# saha-cpu.net
KiCad netlist of a schematic drawn in EAGLE
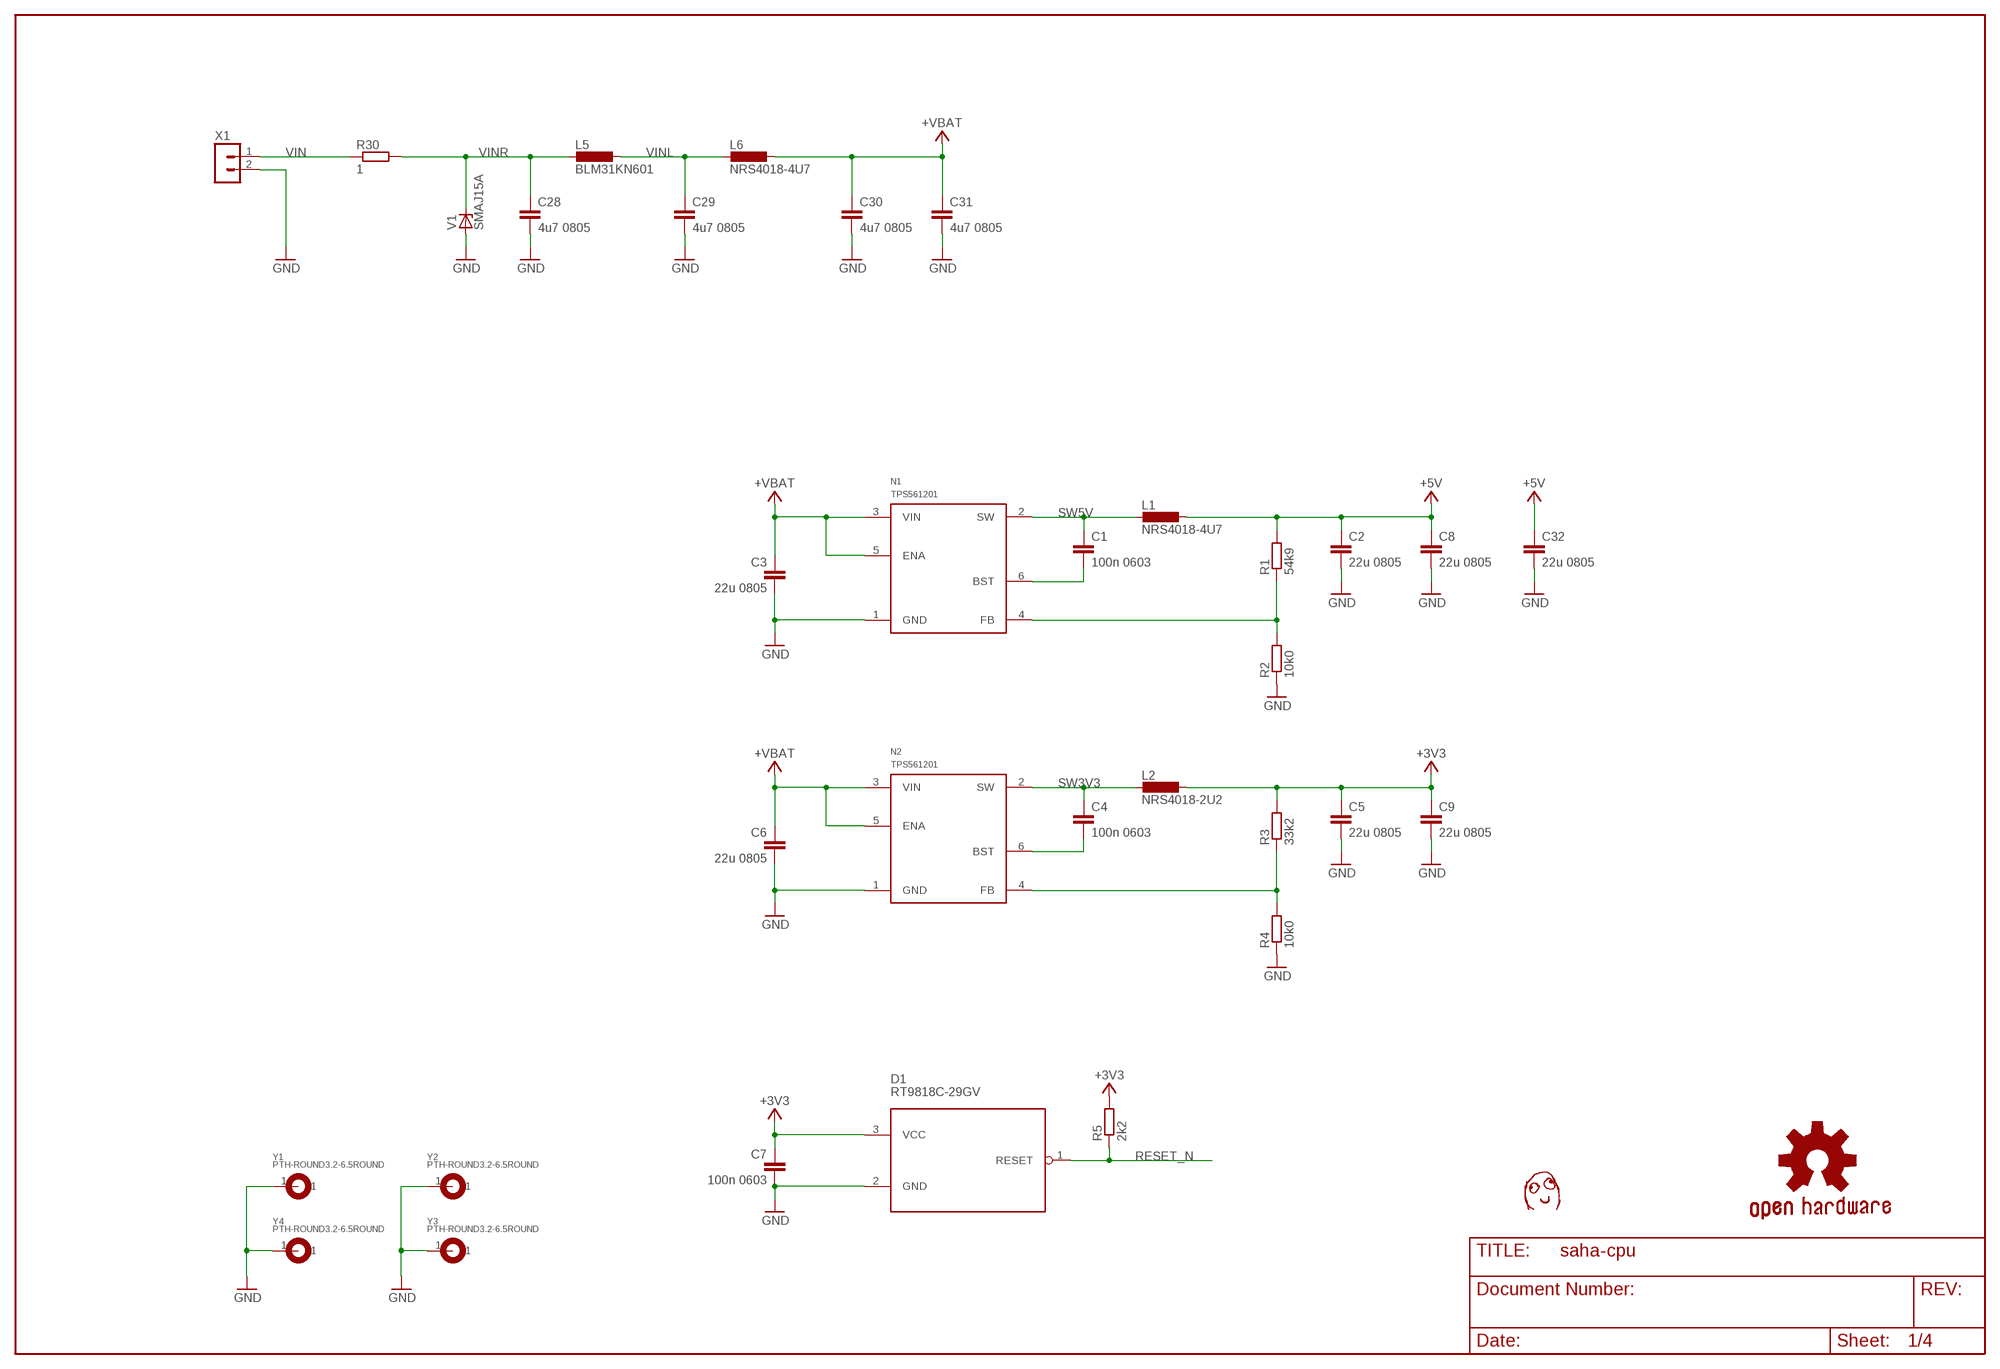
[diagram p0: schematic, sheet 1]
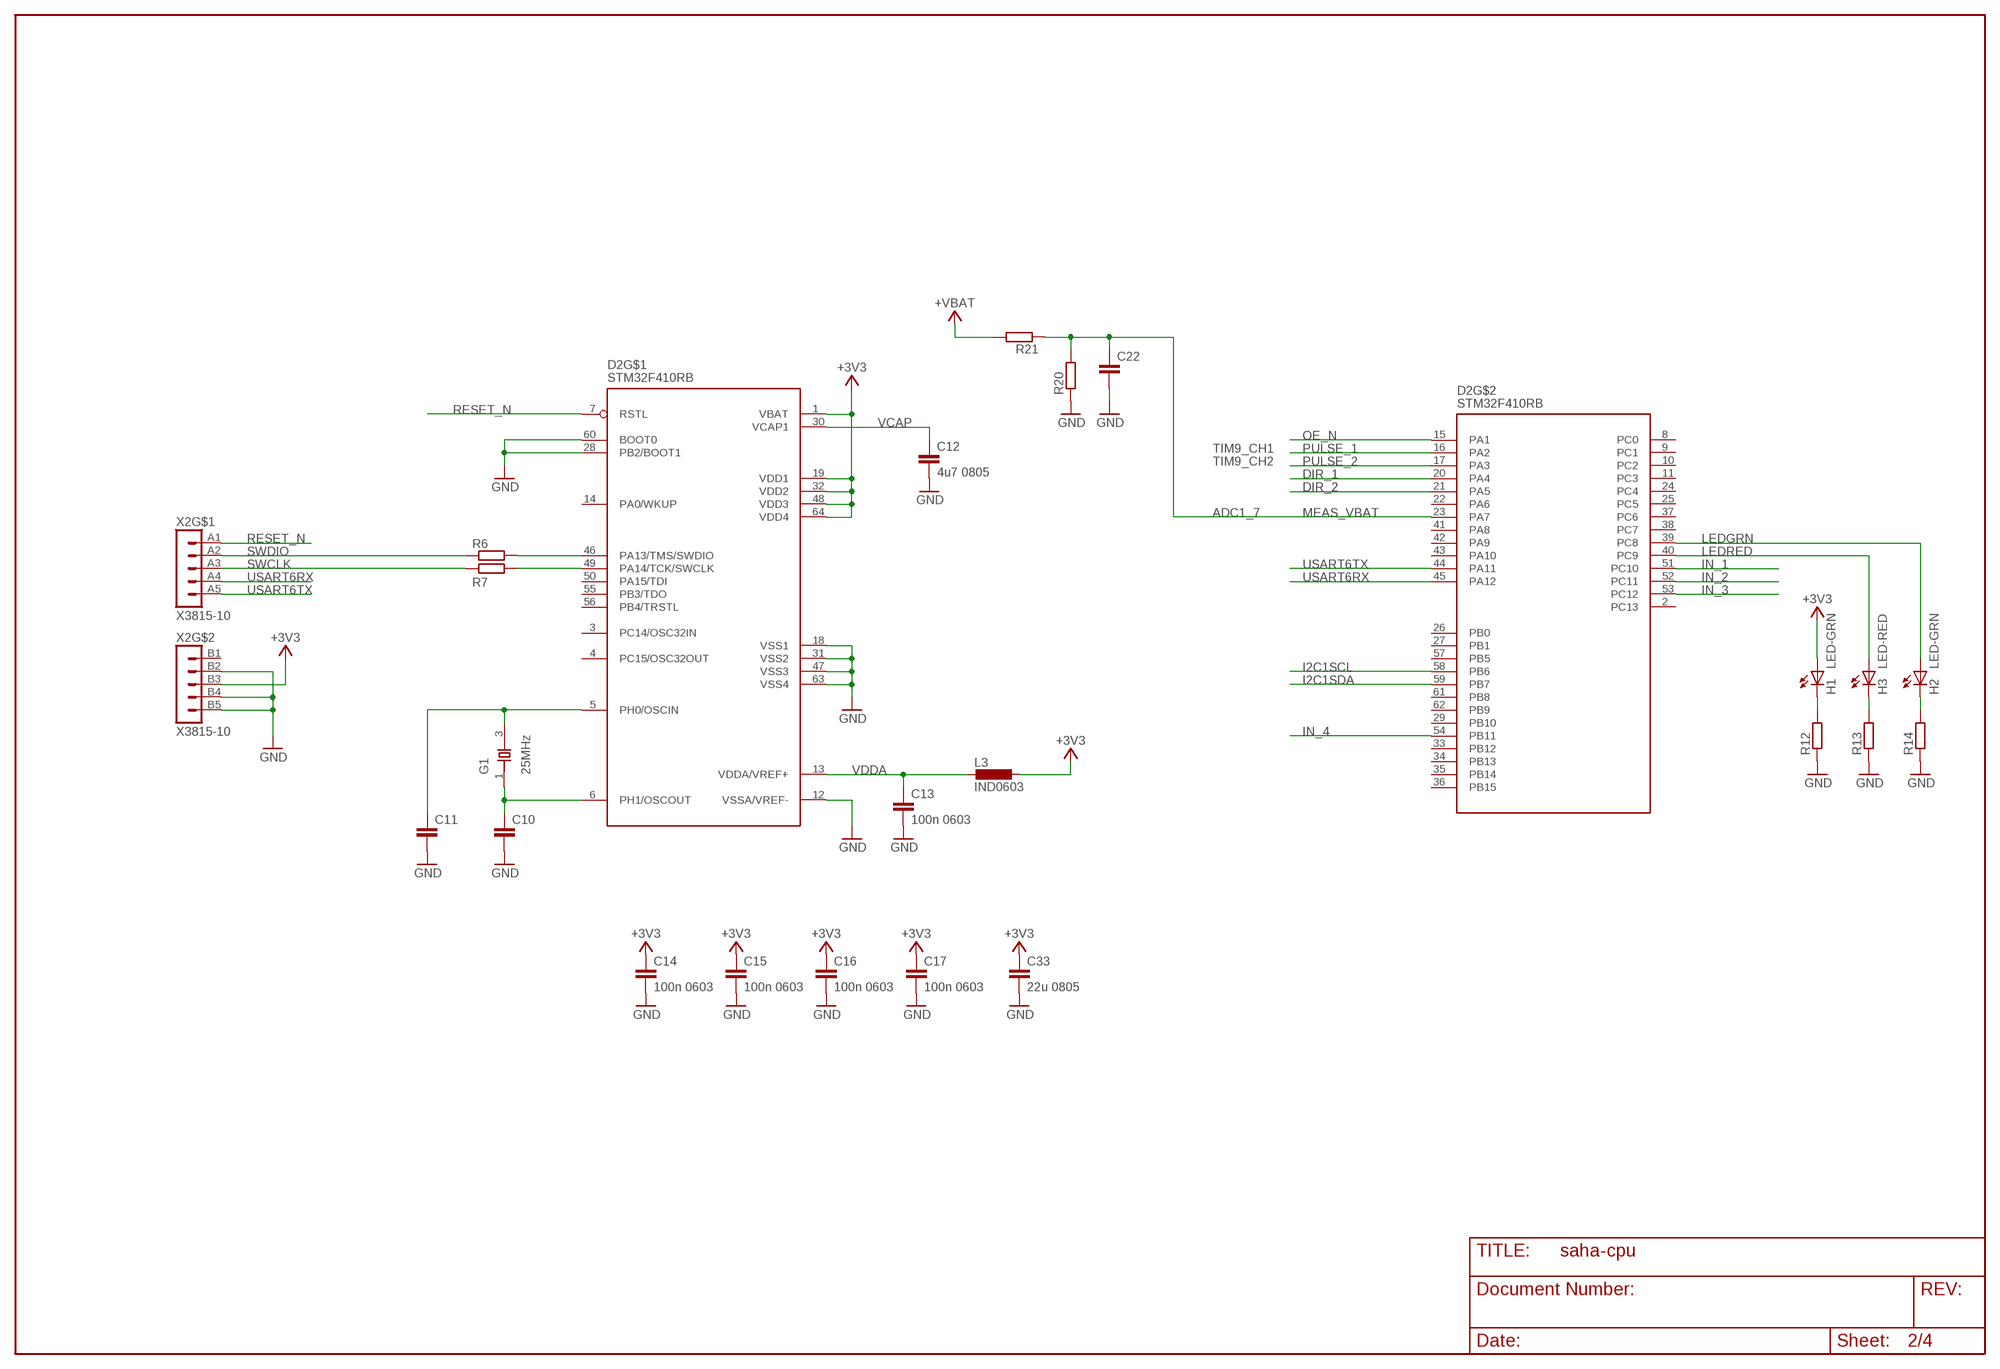
[diagram p1: schematic, sheet 2]
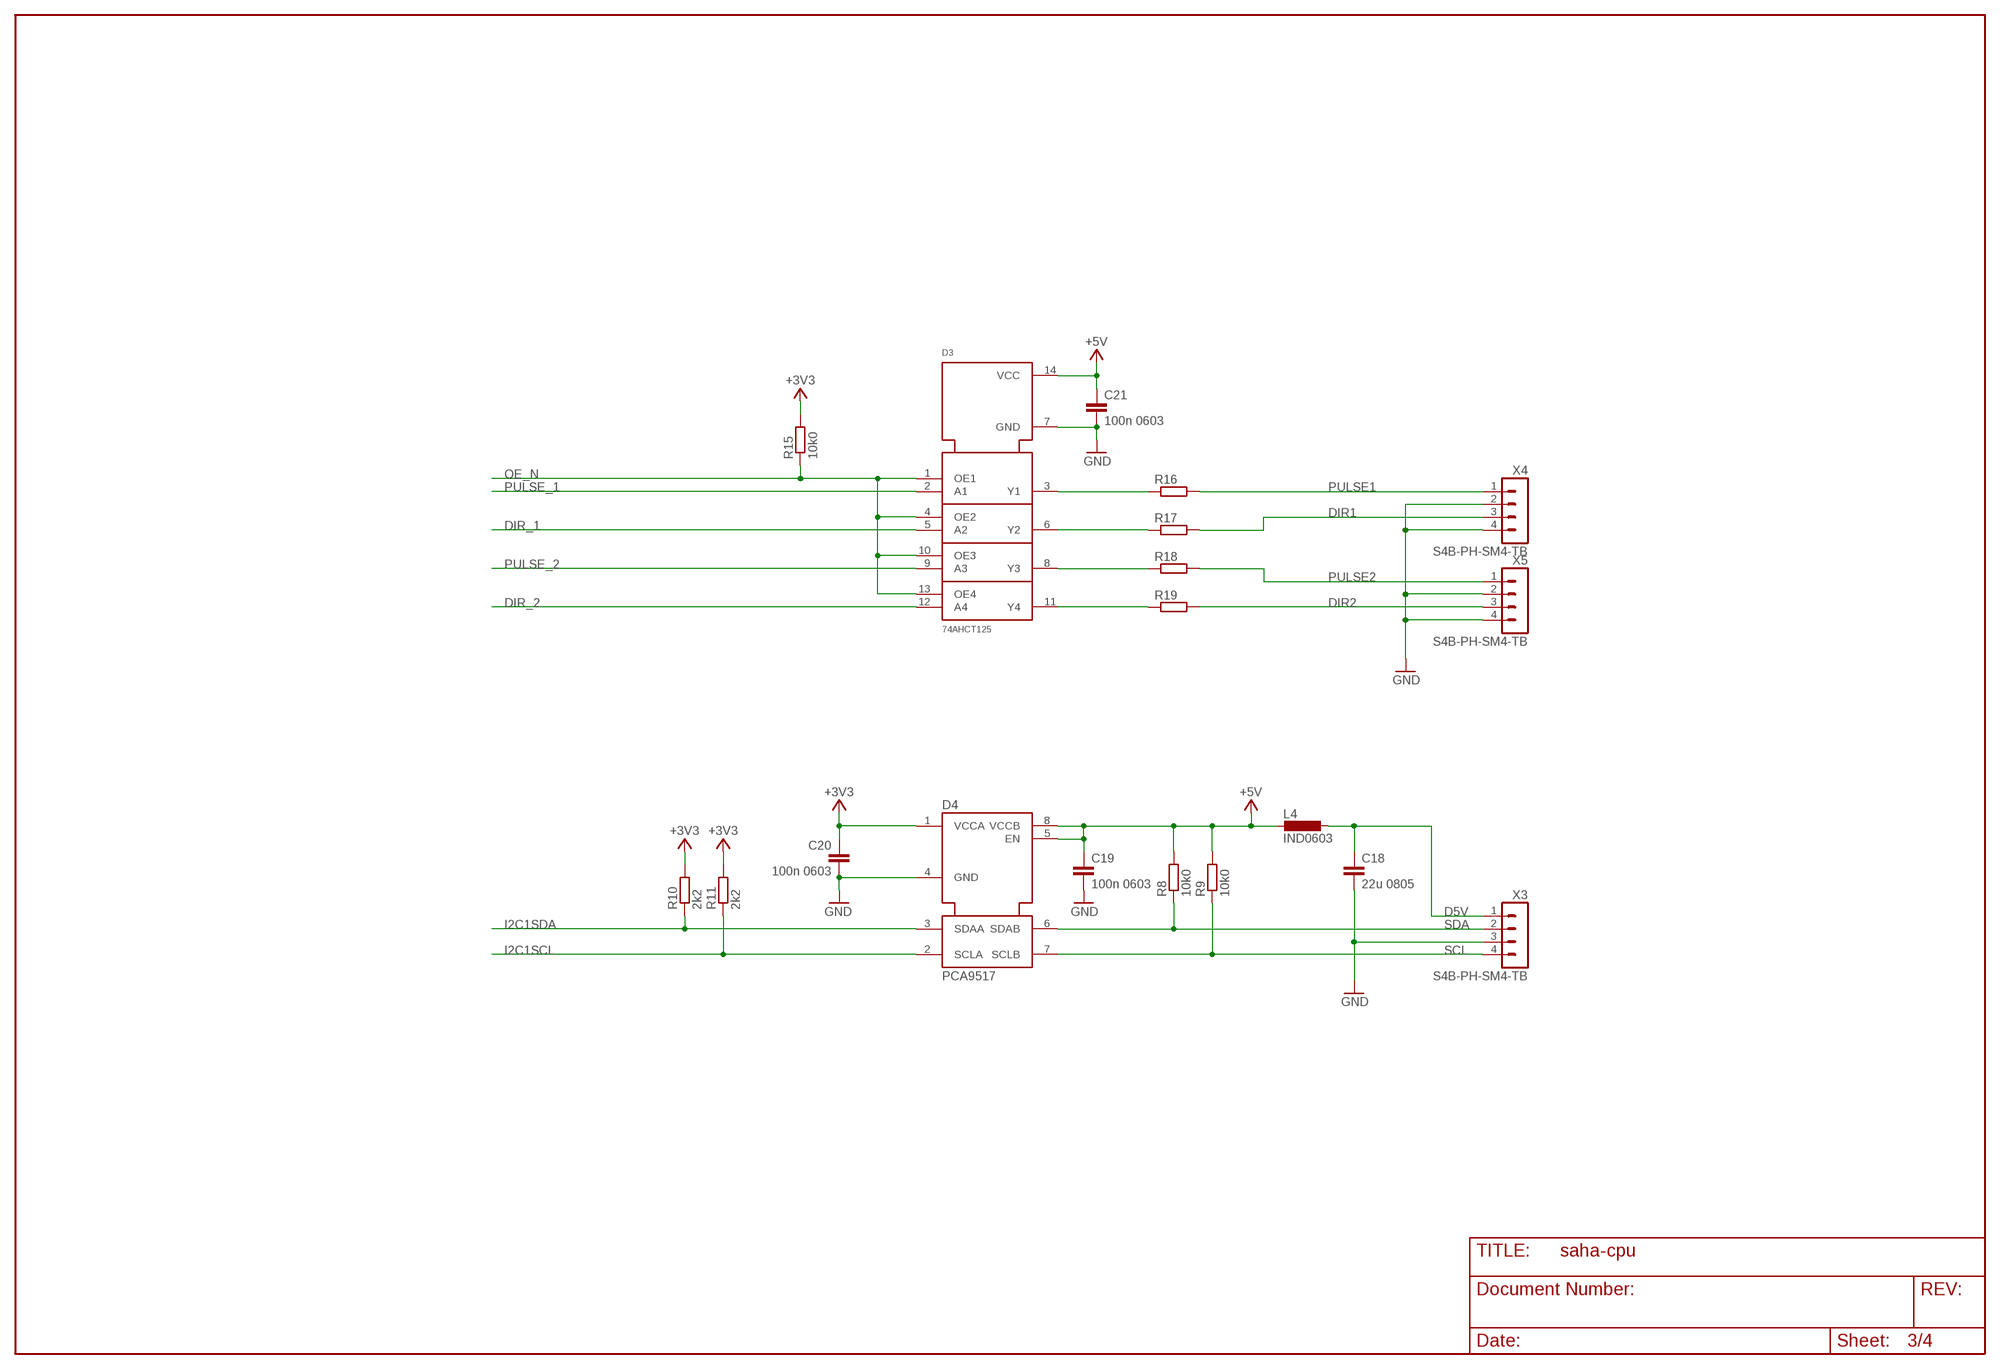
[diagram p2: schematic, sheet 3]
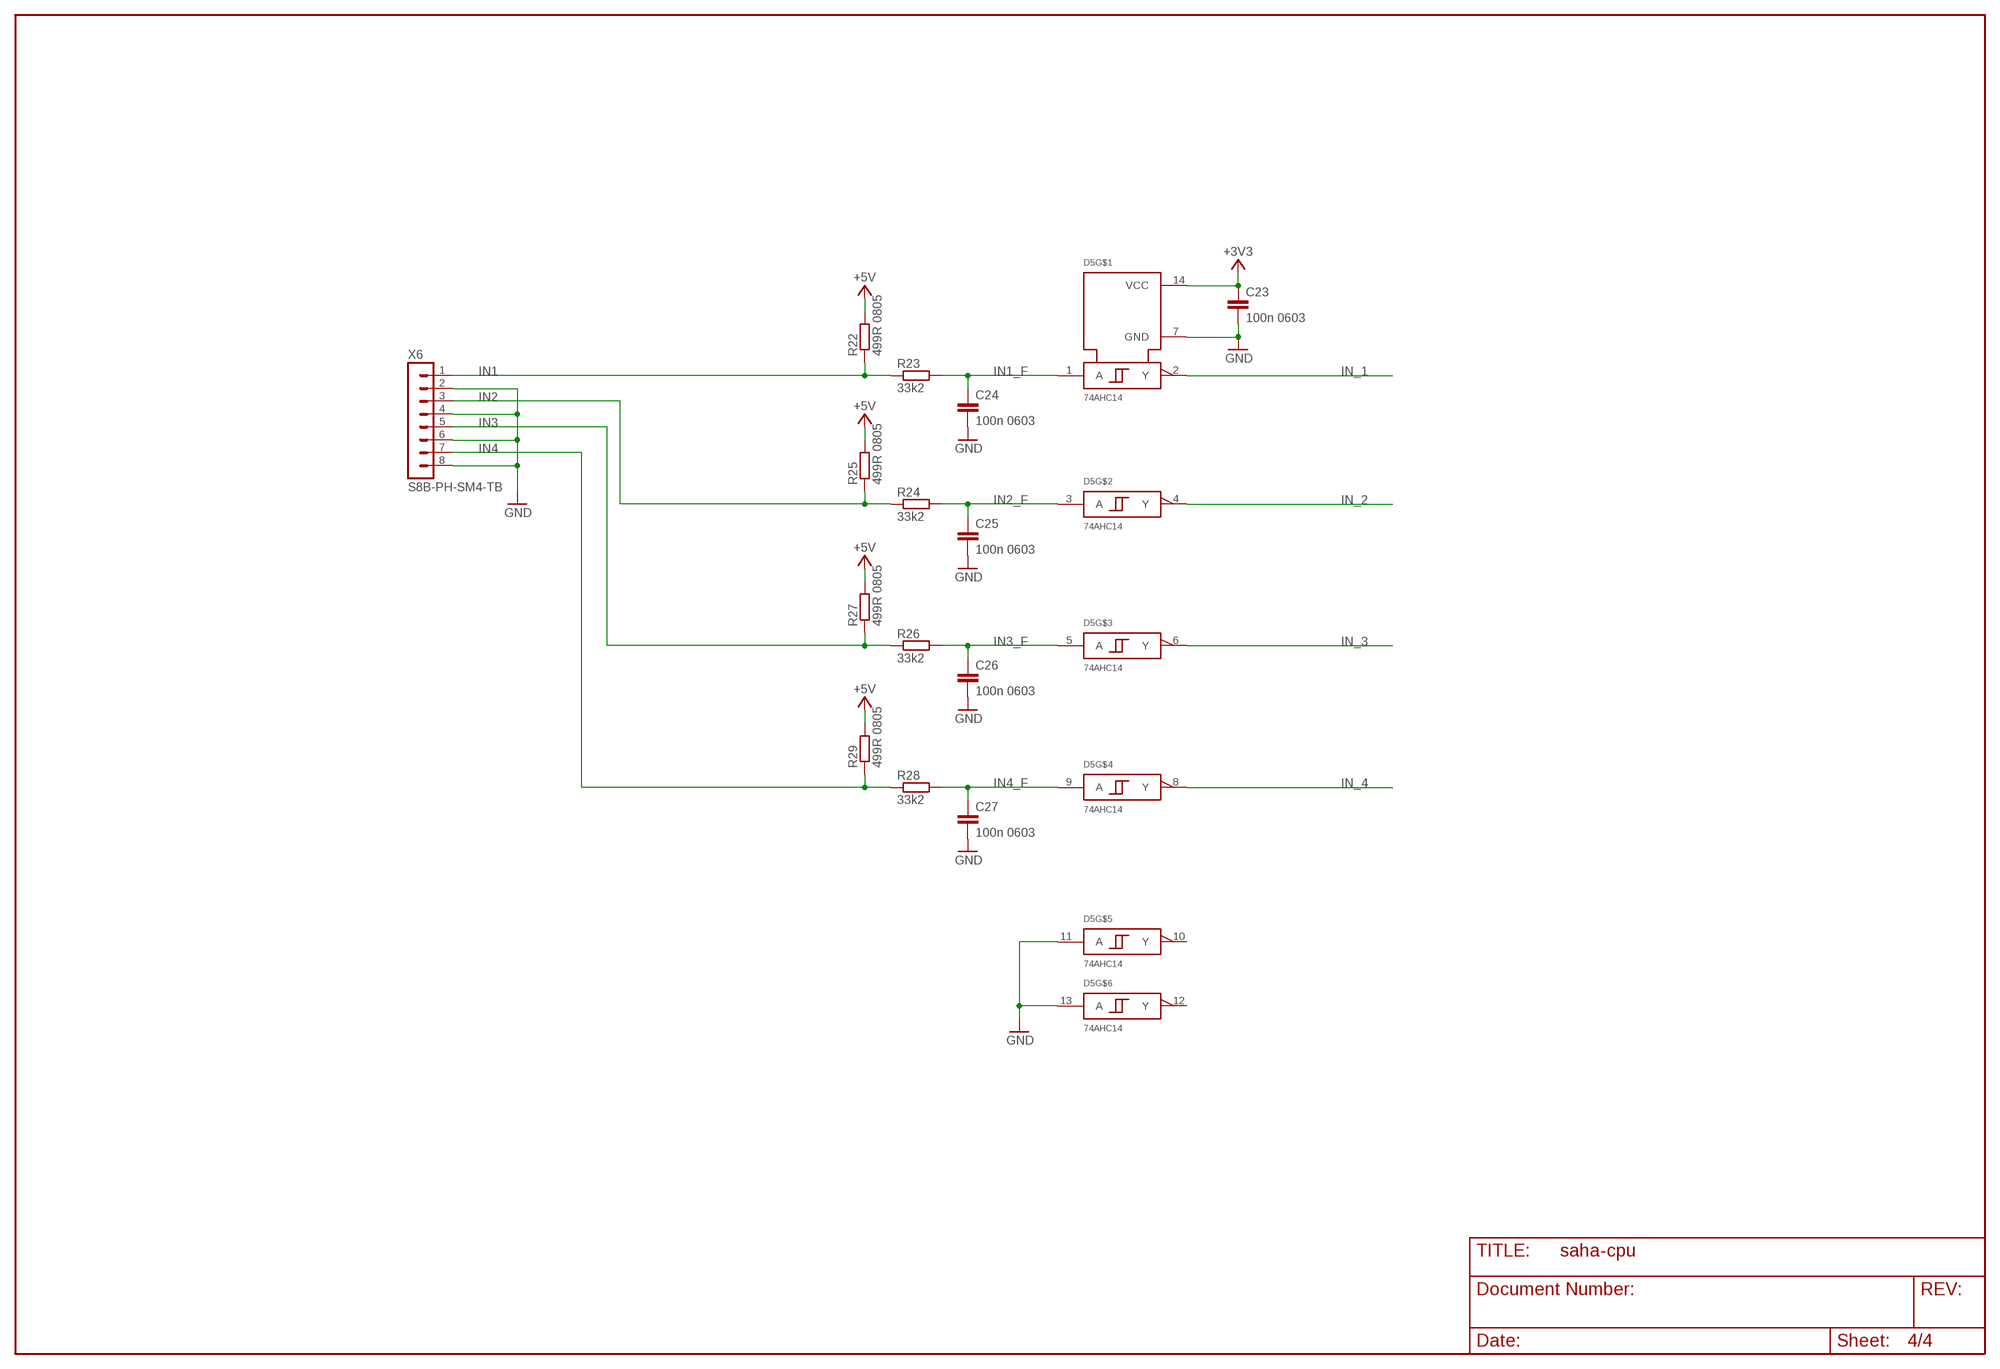
[diagram p3: schematic, sheet 4]

(export (version "E")
  (design (tool "Eeschema 10.0.6"))
  (components
    (comp (ref "C1")
      (value "100n 0603")
      (footprint "eagle-import:C0603")
      (libsource (lib "eagle-import") (part "CAP0603"))
    )
    (comp (ref "C2")
      (value "22u 0805")
      (footprint "eagle-import:C0805")
      (libsource (lib "eagle-import") (part "CAP0805"))
    )
    (comp (ref "C3")
      (value "22u 0805")
      (footprint "eagle-import:C0805")
      (libsource (lib "eagle-import") (part "CAP0805"))
    )
    (comp (ref "C4")
      (value "100n 0603")
      (footprint "eagle-import:C0603")
      (libsource (lib "eagle-import") (part "CAP0603"))
    )
    (comp (ref "C5")
      (value "22u 0805")
      (footprint "eagle-import:C0805")
      (libsource (lib "eagle-import") (part "CAP0805"))
    )
    (comp (ref "C6")
      (value "22u 0805")
      (footprint "eagle-import:C0805")
      (libsource (lib "eagle-import") (part "CAP0805"))
    )
    (comp (ref "C7")
      (value "100n 0603")
      (footprint "eagle-import:C0603")
      (libsource (lib "eagle-import") (part "CAP0603"))
    )
    (comp (ref "C8")
      (value "22u 0805")
      (footprint "eagle-import:C0805")
      (libsource (lib "eagle-import") (part "CAP0805"))
    )
    (comp (ref "C9")
      (value "22u 0805")
      (footprint "eagle-import:C0805")
      (libsource (lib "eagle-import") (part "CAP0805"))
    )
    (comp (ref "C28")
      (value "4u7 0805")
      (footprint "eagle-import:C0805")
      (libsource (lib "eagle-import") (part "CAP0805"))
    )
    (comp (ref "C29")
      (value "4u7 0805")
      (footprint "eagle-import:C0805")
      (libsource (lib "eagle-import") (part "CAP0805"))
    )
    (comp (ref "C30")
      (value "4u7 0805")
      (footprint "eagle-import:C0805")
      (libsource (lib "eagle-import") (part "CAP0805"))
    )
    (comp (ref "C31")
      (value "4u7 0805")
      (footprint "eagle-import:C0805")
      (libsource (lib "eagle-import") (part "CAP0805"))
    )
    (comp (ref "C32")
      (value "22u 0805")
      (footprint "eagle-import:C0805")
      (libsource (lib "eagle-import") (part "CAP0805"))
    )
    (comp (ref "D1")
      (value "RT9818C-29GV")
      (footprint "eagle-import:SOT23")
      (libsource (lib "eagle-import") (part "RT9818C-29GV"))
    )
    (comp (ref "L1")
      (value "NRS4018-4U7")
      (footprint "eagle-import:NRS4018")
      (libsource (lib "eagle-import") (part "NRS4018-4U7"))
    )
    (comp (ref "L2")
      (value "NRS4018-2U2")
      (footprint "eagle-import:NRS4018")
      (libsource (lib "eagle-import") (part "NRS4018-2U2"))
    )
    (comp (ref "L5")
      (value "BLM31KN601")
      (footprint "eagle-import:R1206")
      (libsource (lib "eagle-import") (part "IND1206"))
    )
    (comp (ref "L6")
      (value "NRS4018-4U7")
      (footprint "eagle-import:NRS4018")
      (libsource (lib "eagle-import") (part "NRS4018-4U7"))
    )
    (comp (ref "N1")
      (value "TPS561201")
      (footprint "eagle-import:OMAT_IC_2_SOT23-6")
      (libsource (lib "eagle-import") (part "TPS561201"))
    )
    (comp (ref "N2")
      (value "TPS561201")
      (footprint "eagle-import:OMAT_IC_2_SOT23-6")
      (libsource (lib "eagle-import") (part "TPS561201"))
    )
    (comp (ref "R1")
      (value "54k9")
      (footprint "eagle-import:R0603")
      (libsource (lib "eagle-import") (part "RES0603"))
    )
    (comp (ref "R2")
      (value "10k0")
      (footprint "eagle-import:R0603")
      (libsource (lib "eagle-import") (part "RES0603"))
    )
    (comp (ref "R3")
      (value "33k2")
      (footprint "eagle-import:R0603")
      (libsource (lib "eagle-import") (part "RES0603"))
    )
    (comp (ref "R4")
      (value "10k0")
      (footprint "eagle-import:R0603")
      (libsource (lib "eagle-import") (part "RES0603"))
    )
    (comp (ref "R5")
      (value "2k2")
      (footprint "eagle-import:R0603")
      (libsource (lib "eagle-import") (part "RES0603"))
    )
    (comp (ref "R30")
      (value "1")
      (footprint "eagle-import:R2512")
      (libsource (lib "eagle-import") (part "RES2512"))
    )
    (comp (ref "U$1")
      (value "DAFUG")
      (footprint "eagle-import:DAFUG")
      (libsource (lib "eagle-import") (part "DAFUG"))
    )
    (comp (ref "V1")
      (value "SMAJ15A")
      (footprint "eagle-import:DO214AC")
      (libsource (lib "eagle-import") (part "SMAJXXA"))
    )
    (comp (ref "X1")
      (value "TE_RUUVILIITIN2")
      (footprint "eagle-import:TE_RUUVILIITIN2")
      (libsource (lib "eagle-import") (part "TE_RUUVILIITIN2"))
    )
    (comp (ref "Y1")
      (value "PTH-ROUND3.2-6.5ROUND")
      (footprint "eagle-import:EKE_PTH-3.2-6.5")
      (libsource (lib "eagle-import") (part "PTH-ROUND3.2-6.5ROUND"))
    )
    (comp (ref "Y2")
      (value "PTH-ROUND3.2-6.5ROUND")
      (footprint "eagle-import:EKE_PTH-3.2-6.5")
      (libsource (lib "eagle-import") (part "PTH-ROUND3.2-6.5ROUND"))
    )
    (comp (ref "Y3")
      (value "PTH-ROUND3.2-6.5ROUND")
      (footprint "eagle-import:EKE_PTH-3.2-6.5")
      (libsource (lib "eagle-import") (part "PTH-ROUND3.2-6.5ROUND"))
    )
    (comp (ref "Y4")
      (value "PTH-ROUND3.2-6.5ROUND")
      (footprint "eagle-import:EKE_PTH-3.2-6.5")
      (libsource (lib "eagle-import") (part "PTH-ROUND3.2-6.5ROUND"))
    )
    (comp (ref "C18")
      (value "22u 0805")
      (footprint "eagle-import:C0805")
      (libsource (lib "eagle-import") (part "CAP0805"))
    )
    (comp (ref "C19")
      (value "100n 0603")
      (footprint "eagle-import:C0603")
      (libsource (lib "eagle-import") (part "CAP0603"))
    )
    (comp (ref "C20")
      (value "100n 0603")
      (footprint "eagle-import:C0603")
      (libsource (lib "eagle-import") (part "CAP0603"))
    )
    (comp (ref "C21")
      (value "100n 0603")
      (footprint "eagle-import:C0603")
      (libsource (lib "eagle-import") (part "CAP0603"))
    )
    (comp (ref "D3")
      (value "74AHCT125")
      (footprint "eagle-import:SO14")
      (libsource (lib "eagle-import") (part "74AHCT125"))
    )
    (comp (ref "D4")
      (value "PCA9517")
      (footprint "eagle-import:OMAT_IC_2_SOIC8-N_MC")
      (libsource (lib "eagle-import") (part "PCA9517"))
    )
    (comp (ref "L4")
      (value "IND0603")
      (footprint "eagle-import:R0603")
      (libsource (lib "eagle-import") (part "IND0603"))
    )
    (comp (ref "R8")
      (value "10k0")
      (footprint "eagle-import:R0603")
      (libsource (lib "eagle-import") (part "RES0603"))
    )
    (comp (ref "R9")
      (value "10k0")
      (footprint "eagle-import:R0603")
      (libsource (lib "eagle-import") (part "RES0603"))
    )
    (comp (ref "R10")
      (value "2k2")
      (footprint "eagle-import:R0603")
      (libsource (lib "eagle-import") (part "RES0603"))
    )
    (comp (ref "R11")
      (value "2k2")
      (footprint "eagle-import:R0603")
      (libsource (lib "eagle-import") (part "RES0603"))
    )
    (comp (ref "R15")
      (value "10k0")
      (footprint "eagle-import:R0603")
      (libsource (lib "eagle-import") (part "RES0603"))
    )
    (comp (ref "R16")
      (value "RES0603")
      (footprint "eagle-import:R0603")
      (libsource (lib "eagle-import") (part "RES0603"))
    )
    (comp (ref "R17")
      (value "RES0603")
      (footprint "eagle-import:R0603")
      (libsource (lib "eagle-import") (part "RES0603"))
    )
    (comp (ref "R18")
      (value "RES0603")
      (footprint "eagle-import:R0603")
      (libsource (lib "eagle-import") (part "RES0603"))
    )
    (comp (ref "R19")
      (value "RES0603")
      (footprint "eagle-import:R0603")
      (libsource (lib "eagle-import") (part "RES0603"))
    )
    (comp (ref "X3")
      (value "S4B-PH-SM4-TB")
      (footprint "eagle-import:JST-PH2.0-RA-4")
      (libsource (lib "eagle-import") (part "S4B-PH-SM4-TB"))
    )
    (comp (ref "X4")
      (value "S4B-PH-SM4-TB")
      (footprint "eagle-import:JST-PH2.0-RA-4")
      (libsource (lib "eagle-import") (part "S4B-PH-SM4-TB"))
    )
    (comp (ref "X5")
      (value "S4B-PH-SM4-TB")
      (footprint "eagle-import:JST-PH2.0-RA-4")
      (libsource (lib "eagle-import") (part "S4B-PH-SM4-TB"))
    )
    (comp (ref "C10")
      (value "CAP0603")
      (footprint "eagle-import:C0603")
      (libsource (lib "eagle-import") (part "CAP0603"))
    )
    (comp (ref "C11")
      (value "CAP0603")
      (footprint "eagle-import:C0603")
      (libsource (lib "eagle-import") (part "CAP0603"))
    )
    (comp (ref "C12")
      (value "4u7 0805")
      (footprint "eagle-import:C0805")
      (libsource (lib "eagle-import") (part "CAP0805"))
    )
    (comp (ref "C13")
      (value "100n 0603")
      (footprint "eagle-import:C0603")
      (libsource (lib "eagle-import") (part "CAP0603"))
    )
    (comp (ref "C14")
      (value "100n 0603")
      (footprint "eagle-import:C0603")
      (libsource (lib "eagle-import") (part "CAP0603"))
    )
    (comp (ref "C15")
      (value "100n 0603")
      (footprint "eagle-import:C0603")
      (libsource (lib "eagle-import") (part "CAP0603"))
    )
    (comp (ref "C16")
      (value "100n 0603")
      (footprint "eagle-import:C0603")
      (libsource (lib "eagle-import") (part "CAP0603"))
    )
    (comp (ref "C17")
      (value "100n 0603")
      (footprint "eagle-import:C0603")
      (libsource (lib "eagle-import") (part "CAP0603"))
    )
    (comp (ref "C22")
      (value "CAP0603")
      (footprint "eagle-import:C0603")
      (libsource (lib "eagle-import") (part "CAP0603"))
    )
    (comp (ref "C33")
      (value "22u 0805")
      (footprint "eagle-import:C0805")
      (libsource (lib "eagle-import") (part "CAP0805"))
    )
    (comp (ref "D2")
      (value "STM32F410RB")
      (footprint "eagle-import:LQFP-64")
      (libsource (lib "eagle-import") (part "STM32F410RB"))
    )
    (comp (ref "G1")
      (value "25MHz")
      (footprint "eagle-import:X_3225")
      (libsource (lib "eagle-import") (part "XTAL_3225_SMD"))
    )
    (comp (ref "H1")
      (value "LED-GRN")
      (footprint "eagle-import:CHIP-LED0603")
      (libsource (lib "eagle-import") (part "LED-GRN"))
    )
    (comp (ref "H2")
      (value "LED-GRN")
      (footprint "eagle-import:CHIP-LED0603")
      (libsource (lib "eagle-import") (part "LED-GRN"))
    )
    (comp (ref "H3")
      (value "LED-RED")
      (footprint "eagle-import:CHIP-LED0603")
      (libsource (lib "eagle-import") (part "LED-RED"))
    )
    (comp (ref "L3")
      (value "IND0603")
      (footprint "eagle-import:R0603")
      (libsource (lib "eagle-import") (part "IND0603"))
    )
    (comp (ref "R6")
      (value "RES0603")
      (footprint "eagle-import:R0603")
      (libsource (lib "eagle-import") (part "RES0603"))
    )
    (comp (ref "R7")
      (value "RES0603")
      (footprint "eagle-import:R0603")
      (libsource (lib "eagle-import") (part "RES0603"))
    )
    (comp (ref "R12")
      (value "RES0603")
      (footprint "eagle-import:R0603")
      (libsource (lib "eagle-import") (part "RES0603"))
    )
    (comp (ref "R13")
      (value "RES0603")
      (footprint "eagle-import:R0603")
      (libsource (lib "eagle-import") (part "RES0603"))
    )
    (comp (ref "R14")
      (value "RES0603")
      (footprint "eagle-import:R0603")
      (libsource (lib "eagle-import") (part "RES0603"))
    )
    (comp (ref "R20")
      (value "RES0603")
      (footprint "eagle-import:R0603")
      (libsource (lib "eagle-import") (part "RES0603"))
    )
    (comp (ref "R21")
      (value "RES0603")
      (footprint "eagle-import:R0603")
      (libsource (lib "eagle-import") (part "RES0603"))
    )
    (comp (ref "X2")
      (value "X3815-10")
      (footprint "eagle-import:AUX-IO_LIITTIMET_15110102601")
      (libsource (lib "eagle-import") (part "X3815-10"))
    )
    (comp (ref "C23")
      (value "100n 0603")
      (footprint "eagle-import:C0603")
      (libsource (lib "eagle-import") (part "CAP0603"))
    )
    (comp (ref "C24")
      (value "100n 0603")
      (footprint "eagle-import:C0603")
      (libsource (lib "eagle-import") (part "CAP0603"))
    )
    (comp (ref "C25")
      (value "100n 0603")
      (footprint "eagle-import:C0603")
      (libsource (lib "eagle-import") (part "CAP0603"))
    )
    (comp (ref "C26")
      (value "100n 0603")
      (footprint "eagle-import:C0603")
      (libsource (lib "eagle-import") (part "CAP0603"))
    )
    (comp (ref "C27")
      (value "100n 0603")
      (footprint "eagle-import:C0603")
      (libsource (lib "eagle-import") (part "CAP0603"))
    )
    (comp (ref "D5")
      (value "74AHC14")
      (footprint "eagle-import:SO14")
      (libsource (lib "eagle-import") (part "74AHC14"))
    )
    (comp (ref "R22")
      (value "499R 0805")
      (footprint "eagle-import:R0805")
      (libsource (lib "eagle-import") (part "RES0805"))
    )
    (comp (ref "R23")
      (value "33k2")
      (footprint "eagle-import:R0603")
      (libsource (lib "eagle-import") (part "RES0603"))
    )
    (comp (ref "R24")
      (value "33k2")
      (footprint "eagle-import:R0603")
      (libsource (lib "eagle-import") (part "RES0603"))
    )
    (comp (ref "R25")
      (value "499R 0805")
      (footprint "eagle-import:R0805")
      (libsource (lib "eagle-import") (part "RES0805"))
    )
    (comp (ref "R26")
      (value "33k2")
      (footprint "eagle-import:R0603")
      (libsource (lib "eagle-import") (part "RES0603"))
    )
    (comp (ref "R27")
      (value "499R 0805")
      (footprint "eagle-import:R0805")
      (libsource (lib "eagle-import") (part "RES0805"))
    )
    (comp (ref "R28")
      (value "33k2")
      (footprint "eagle-import:R0603")
      (libsource (lib "eagle-import") (part "RES0603"))
    )
    (comp (ref "R29")
      (value "499R 0805")
      (footprint "eagle-import:R0805")
      (libsource (lib "eagle-import") (part "RES0805"))
    )
    (comp (ref "X6")
      (value "S8B-PH-SM4-TB")
      (footprint "eagle-import:JST-PH2.0-RA-8")
      (libsource (lib "eagle-import") (part "S8B-PH-SM4-TB"))
    )
  )
  (nets
    (net (code "1") (name "+3V3") (class "Default")
      (node (ref "C14") (pin "1") (pinfunction "1_1") (pintype "passive"))
      (node (ref "C15") (pin "1") (pinfunction "1_1") (pintype "passive"))
      (node (ref "C16") (pin "1") (pinfunction "1_1") (pintype "passive"))
      (node (ref "C17") (pin "1") (pinfunction "1_1") (pintype "passive"))
      (node (ref "C20") (pin "1") (pinfunction "1_1") (pintype "passive"))
      (node (ref "C23") (pin "1") (pinfunction "1_1") (pintype "passive"))
      (node (ref "C33") (pin "1") (pinfunction "1_1") (pintype "passive"))
      (node (ref "C5") (pin "1") (pinfunction "1_1") (pintype "passive"))
      (node (ref "C7") (pin "1") (pinfunction "1_1") (pintype "passive"))
      (node (ref "C9") (pin "1") (pinfunction "1_1") (pintype "passive"))
      (node (ref "D1") (pin "3") (pinfunction "VCC_3") (pintype "bidirectional"))
      (node (ref "D2") (pin "1") (pinfunction "VBAT_1") (pintype "bidirectional"))
      (node (ref "D2") (pin "19") (pinfunction "VDD1_19") (pintype "bidirectional"))
      (node (ref "D2") (pin "32") (pinfunction "VDD2_32") (pintype "bidirectional"))
      (node (ref "D2") (pin "48") (pinfunction "VDD3_48") (pintype "bidirectional"))
      (node (ref "D2") (pin "64") (pinfunction "VDD4_64") (pintype "bidirectional"))
      (node (ref "D4") (pin "1") (pinfunction "VCCA_1") (pintype "bidirectional"))
      (node (ref "D5") (pin "14") (pinfunction "VCC_14") (pintype "bidirectional"))
      (node (ref "H1") (pin "A") (pinfunction "A_A") (pintype "passive"))
      (node (ref "L2") (pin "1") (pinfunction "1_1") (pintype "passive"))
      (node (ref "L3") (pin "1") (pinfunction "1_1") (pintype "passive"))
      (node (ref "R10") (pin "2") (pinfunction "2_2") (pintype "passive"))
      (node (ref "R11") (pin "2") (pinfunction "2_2") (pintype "passive"))
      (node (ref "R15") (pin "2") (pinfunction "2_2") (pintype "passive"))
      (node (ref "R3") (pin "2") (pinfunction "2_2") (pintype "passive"))
      (node (ref "R5") (pin "2") (pinfunction "2_2") (pintype "passive"))
      (node (ref "X2") (pin "B3") (pinfunction "3_B3") (pintype "passive"))
    )
    (net (code "2") (name "+5V") (class "Default")
      (node (ref "C19") (pin "1") (pinfunction "1_1") (pintype "passive"))
      (node (ref "C2") (pin "1") (pinfunction "1_1") (pintype "passive"))
      (node (ref "C21") (pin "1") (pinfunction "1_1") (pintype "passive"))
      (node (ref "C32") (pin "1") (pinfunction "1_1") (pintype "passive"))
      (node (ref "C8") (pin "1") (pinfunction "1_1") (pintype "passive"))
      (node (ref "D3") (pin "14") (pinfunction "VCC_14") (pintype "bidirectional"))
      (node (ref "D4") (pin "5") (pinfunction "EN_5") (pintype "bidirectional"))
      (node (ref "D4") (pin "8") (pinfunction "VCCB_8") (pintype "bidirectional"))
      (node (ref "L1") (pin "1") (pinfunction "1_1") (pintype "passive"))
      (node (ref "L4") (pin "2") (pinfunction "2_2") (pintype "passive"))
      (node (ref "R1") (pin "2") (pinfunction "2_2") (pintype "passive"))
      (node (ref "R22") (pin "2") (pinfunction "2_2") (pintype "passive"))
      (node (ref "R25") (pin "2") (pinfunction "2_2") (pintype "passive"))
      (node (ref "R27") (pin "2") (pinfunction "2_2") (pintype "passive"))
      (node (ref "R29") (pin "2") (pinfunction "2_2") (pintype "passive"))
      (node (ref "R8") (pin "2") (pinfunction "2_2") (pintype "passive"))
      (node (ref "R9") (pin "2") (pinfunction "2_2") (pintype "passive"))
    )
    (net (code "3") (name "+VBAT") (class "Default")
      (node (ref "C3") (pin "1") (pinfunction "1_1") (pintype "passive"))
      (node (ref "C30") (pin "1") (pinfunction "1_1") (pintype "passive"))
      (node (ref "C31") (pin "1") (pinfunction "1_1") (pintype "passive"))
      (node (ref "C6") (pin "1") (pinfunction "1_1") (pintype "passive"))
      (node (ref "L6") (pin "1") (pinfunction "1_1") (pintype "passive"))
      (node (ref "N1") (pin "3") (pinfunction "VIN_3") (pintype "bidirectional"))
      (node (ref "N1") (pin "5") (pinfunction "ENA_5") (pintype "bidirectional"))
      (node (ref "N2") (pin "3") (pinfunction "VIN_3") (pintype "bidirectional"))
      (node (ref "N2") (pin "5") (pinfunction "ENA_5") (pintype "bidirectional"))
      (node (ref "R21") (pin "2") (pinfunction "2_2") (pintype "passive"))
    )
    (net (code "4") (name "D5V") (class "Default")
      (node (ref "C18") (pin "1") (pinfunction "1_1") (pintype "passive"))
      (node (ref "L4") (pin "1") (pinfunction "1_1") (pintype "passive"))
      (node (ref "X3") (pin "1") (pinfunction "1_1") (pintype "passive"))
    )
    (net (code "5") (name "DIR1") (class "Default")
      (node (ref "R17") (pin "2") (pinfunction "2_2") (pintype "passive"))
      (node (ref "X4") (pin "3") (pinfunction "3_3") (pintype "passive"))
    )
    (net (code "6") (name "DIR2") (class "Default")
      (node (ref "R19") (pin "2") (pinfunction "2_2") (pintype "passive"))
      (node (ref "X5") (pin "3") (pinfunction "3_3") (pintype "passive"))
    )
    (net (code "7") (name "DIR_1") (class "Default")
      (node (ref "D2") (pin "20") (pinfunction "PA4_20") (pintype "bidirectional"))
      (node (ref "D3") (pin "5") (pinfunction "A2_5") (pintype "bidirectional"))
    )
    (net (code "8") (name "DIR_2") (class "Default")
      (node (ref "D2") (pin "21") (pinfunction "PA5_21") (pintype "bidirectional"))
      (node (ref "D3") (pin "12") (pinfunction "A4_12") (pintype "bidirectional"))
    )
    (net (code "9") (name "GND") (class "Default")
      (node (ref "C10") (pin "2") (pinfunction "2_2") (pintype "passive"))
      (node (ref "C11") (pin "2") (pinfunction "2_2") (pintype "passive"))
      (node (ref "C12") (pin "2") (pinfunction "2_2") (pintype "passive"))
      (node (ref "C13") (pin "2") (pinfunction "2_2") (pintype "passive"))
      (node (ref "C14") (pin "2") (pinfunction "2_2") (pintype "passive"))
      (node (ref "C15") (pin "2") (pinfunction "2_2") (pintype "passive"))
      (node (ref "C16") (pin "2") (pinfunction "2_2") (pintype "passive"))
      (node (ref "C17") (pin "2") (pinfunction "2_2") (pintype "passive"))
      (node (ref "C18") (pin "2") (pinfunction "2_2") (pintype "passive"))
      (node (ref "C19") (pin "2") (pinfunction "2_2") (pintype "passive"))
      (node (ref "C2") (pin "2") (pinfunction "2_2") (pintype "passive"))
      (node (ref "C20") (pin "2") (pinfunction "2_2") (pintype "passive"))
      (node (ref "C21") (pin "2") (pinfunction "2_2") (pintype "passive"))
      (node (ref "C22") (pin "2") (pinfunction "2_2") (pintype "passive"))
      (node (ref "C23") (pin "2") (pinfunction "2_2") (pintype "passive"))
      (node (ref "C24") (pin "2") (pinfunction "2_2") (pintype "passive"))
      (node (ref "C25") (pin "2") (pinfunction "2_2") (pintype "passive"))
      (node (ref "C26") (pin "2") (pinfunction "2_2") (pintype "passive"))
      (node (ref "C27") (pin "2") (pinfunction "2_2") (pintype "passive"))
      (node (ref "C28") (pin "2") (pinfunction "2_2") (pintype "passive"))
      (node (ref "C29") (pin "2") (pinfunction "2_2") (pintype "passive"))
      (node (ref "C3") (pin "2") (pinfunction "2_2") (pintype "passive"))
      (node (ref "C30") (pin "2") (pinfunction "2_2") (pintype "passive"))
      (node (ref "C31") (pin "2") (pinfunction "2_2") (pintype "passive"))
      (node (ref "C32") (pin "2") (pinfunction "2_2") (pintype "passive"))
      (node (ref "C33") (pin "2") (pinfunction "2_2") (pintype "passive"))
      (node (ref "C5") (pin "2") (pinfunction "2_2") (pintype "passive"))
      (node (ref "C6") (pin "2") (pinfunction "2_2") (pintype "passive"))
      (node (ref "C7") (pin "2") (pinfunction "2_2") (pintype "passive"))
      (node (ref "C8") (pin "2") (pinfunction "2_2") (pintype "passive"))
      (node (ref "C9") (pin "2") (pinfunction "2_2") (pintype "passive"))
      (node (ref "D1") (pin "2") (pinfunction "GND_2") (pintype "bidirectional"))
      (node (ref "D2") (pin "12") (pinfunction "VSSA/VREF-_12") (pintype "bidirectional"))
      (node (ref "D2") (pin "18") (pinfunction "VSS1_18") (pintype "bidirectional"))
      (node (ref "D2") (pin "28") (pinfunction "PB2/BOOT1_28") (pintype "bidirectional"))
      (node (ref "D2") (pin "31") (pinfunction "VSS2_31") (pintype "bidirectional"))
      (node (ref "D2") (pin "47") (pinfunction "VSS3_47") (pintype "bidirectional"))
      (node (ref "D2") (pin "60") (pinfunction "BOOT0_60") (pintype "bidirectional"))
      (node (ref "D2") (pin "63") (pinfunction "VSS4_63") (pintype "bidirectional"))
      (node (ref "D3") (pin "7") (pinfunction "GND_7") (pintype "bidirectional"))
      (node (ref "D4") (pin "4") (pinfunction "GND_4") (pintype "bidirectional"))
      (node (ref "D5") (pin "11") (pinfunction "A_11") (pintype "bidirectional"))
      (node (ref "D5") (pin "13") (pinfunction "A_13") (pintype "bidirectional"))
      (node (ref "D5") (pin "7") (pinfunction "GND_7") (pintype "bidirectional"))
      (node (ref "N1") (pin "1") (pinfunction "GND_1") (pintype "bidirectional"))
      (node (ref "N2") (pin "1") (pinfunction "GND_1") (pintype "bidirectional"))
      (node (ref "R12") (pin "1") (pinfunction "1_1") (pintype "passive"))
      (node (ref "R13") (pin "1") (pinfunction "1_1") (pintype "passive"))
      (node (ref "R14") (pin "1") (pinfunction "1_1") (pintype "passive"))
      (node (ref "R2") (pin "1") (pinfunction "1_1") (pintype "passive"))
      (node (ref "R20") (pin "1") (pinfunction "1_1") (pintype "passive"))
      (node (ref "R4") (pin "1") (pinfunction "1_1") (pintype "passive"))
      (node (ref "V1") (pin "A") (pinfunction "A_A") (pintype "passive"))
      (node (ref "X1") (pin "2") (pinfunction "2_2") (pintype "passive"))
      (node (ref "X2") (pin "B2") (pinfunction "2_B2") (pintype "passive"))
      (node (ref "X2") (pin "B4") (pinfunction "4_B4") (pintype "passive"))
      (node (ref "X2") (pin "B5") (pinfunction "5_B5") (pintype "passive"))
      (node (ref "X3") (pin "3") (pinfunction "3_3") (pintype "passive"))
      (node (ref "X4") (pin "2") (pinfunction "2_2") (pintype "passive"))
      (node (ref "X4") (pin "4") (pinfunction "4_4") (pintype "passive"))
      (node (ref "X5") (pin "2") (pinfunction "2_2") (pintype "passive"))
      (node (ref "X5") (pin "4") (pinfunction "4_4") (pintype "passive"))
      (node (ref "X6") (pin "2") (pinfunction "2_2") (pintype "passive"))
      (node (ref "X6") (pin "4") (pinfunction "4_4") (pintype "passive"))
      (node (ref "X6") (pin "6") (pinfunction "6_6") (pintype "passive"))
      (node (ref "X6") (pin "8") (pinfunction "8_8") (pintype "passive"))
      (node (ref "Y1") (pin "1") (pinfunction "1_1") (pintype "bidirectional"))
      (node (ref "Y2") (pin "1") (pinfunction "1_1") (pintype "bidirectional"))
      (node (ref "Y3") (pin "1") (pinfunction "1_1") (pintype "bidirectional"))
      (node (ref "Y4") (pin "1") (pinfunction "1_1") (pintype "bidirectional"))
    )
    (net (code "10") (name "I2C1SCL") (class "Default")
      (node (ref "D2") (pin "58") (pinfunction "PB6_58") (pintype "bidirectional"))
      (node (ref "D4") (pin "2") (pinfunction "SCLA_2") (pintype "bidirectional"))
      (node (ref "R11") (pin "1") (pinfunction "1_1") (pintype "passive"))
    )
    (net (code "11") (name "I2C1SDA") (class "Default")
      (node (ref "D2") (pin "59") (pinfunction "PB7_59") (pintype "bidirectional"))
      (node (ref "D4") (pin "3") (pinfunction "SDAA_3") (pintype "bidirectional"))
      (node (ref "R10") (pin "1") (pinfunction "1_1") (pintype "passive"))
    )
    (net (code "12") (name "IN1") (class "Default")
      (node (ref "R22") (pin "1") (pinfunction "1_1") (pintype "passive"))
      (node (ref "R23") (pin "1") (pinfunction "1_1") (pintype "passive"))
      (node (ref "X6") (pin "1") (pinfunction "1_1") (pintype "passive"))
    )
    (net (code "13") (name "IN1_F") (class "Default")
      (node (ref "C24") (pin "1") (pinfunction "1_1") (pintype "passive"))
      (node (ref "D5") (pin "1") (pinfunction "A_1") (pintype "bidirectional"))
      (node (ref "R23") (pin "2") (pinfunction "2_2") (pintype "passive"))
    )
    (net (code "14") (name "IN2") (class "Default")
      (node (ref "R24") (pin "1") (pinfunction "1_1") (pintype "passive"))
      (node (ref "R25") (pin "1") (pinfunction "1_1") (pintype "passive"))
      (node (ref "X6") (pin "3") (pinfunction "3_3") (pintype "passive"))
    )
    (net (code "15") (name "IN2_F") (class "Default")
      (node (ref "C25") (pin "1") (pinfunction "1_1") (pintype "passive"))
      (node (ref "D5") (pin "3") (pinfunction "A_3") (pintype "bidirectional"))
      (node (ref "R24") (pin "2") (pinfunction "2_2") (pintype "passive"))
    )
    (net (code "16") (name "IN3") (class "Default")
      (node (ref "R26") (pin "1") (pinfunction "1_1") (pintype "passive"))
      (node (ref "R27") (pin "1") (pinfunction "1_1") (pintype "passive"))
      (node (ref "X6") (pin "5") (pinfunction "5_5") (pintype "passive"))
    )
    (net (code "17") (name "IN3_F") (class "Default")
      (node (ref "C26") (pin "1") (pinfunction "1_1") (pintype "passive"))
      (node (ref "D5") (pin "5") (pinfunction "A_5") (pintype "bidirectional"))
      (node (ref "R26") (pin "2") (pinfunction "2_2") (pintype "passive"))
    )
    (net (code "18") (name "IN4") (class "Default")
      (node (ref "R28") (pin "1") (pinfunction "1_1") (pintype "passive"))
      (node (ref "R29") (pin "1") (pinfunction "1_1") (pintype "passive"))
      (node (ref "X6") (pin "7") (pinfunction "7_7") (pintype "passive"))
    )
    (net (code "19") (name "IN4_F") (class "Default")
      (node (ref "C27") (pin "1") (pinfunction "1_1") (pintype "passive"))
      (node (ref "D5") (pin "9") (pinfunction "A_9") (pintype "bidirectional"))
      (node (ref "R28") (pin "2") (pinfunction "2_2") (pintype "passive"))
    )
    (net (code "20") (name "IN_1") (class "Default")
      (node (ref "D2") (pin "51") (pinfunction "PC10_51") (pintype "bidirectional"))
      (node (ref "D5") (pin "2") (pinfunction "Y_2") (pintype "bidirectional"))
    )
    (net (code "21") (name "IN_2") (class "Default")
      (node (ref "D2") (pin "52") (pinfunction "PC11_52") (pintype "bidirectional"))
      (node (ref "D5") (pin "4") (pinfunction "Y_4") (pintype "bidirectional"))
    )
    (net (code "22") (name "IN_3") (class "Default")
      (node (ref "D2") (pin "53") (pinfunction "PC12_53") (pintype "bidirectional"))
      (node (ref "D5") (pin "6") (pinfunction "Y_6") (pintype "bidirectional"))
    )
    (net (code "23") (name "IN_4") (class "Default")
      (node (ref "D2") (pin "54") (pinfunction "PB11_54") (pintype "bidirectional"))
      (node (ref "D5") (pin "8") (pinfunction "Y_8") (pintype "bidirectional"))
    )
    (net (code "24") (name "LEDGRN") (class "Default")
      (node (ref "D2") (pin "39") (pinfunction "PC8_39") (pintype "bidirectional"))
      (node (ref "H2") (pin "A") (pinfunction "A_A") (pintype "passive"))
    )
    (net (code "25") (name "LEDRED") (class "Default")
      (node (ref "D2") (pin "40") (pinfunction "PC9_40") (pintype "bidirectional"))
      (node (ref "H3") (pin "A") (pinfunction "A_A") (pintype "passive"))
    )
    (net (code "26") (name "MEAS_VBAT") (class "Default")
      (node (ref "C22") (pin "1") (pinfunction "1_1") (pintype "passive"))
      (node (ref "D2") (pin "23") (pinfunction "PA7_23") (pintype "bidirectional"))
      (node (ref "R20") (pin "2") (pinfunction "2_2") (pintype "passive"))
      (node (ref "R21") (pin "1") (pinfunction "1_1") (pintype "passive"))
    )
    (net (code "27") (name "Net-(D2A-PA13{slash}TMS{slash}SWDIO)") (class "Default")
      (node (ref "D2") (pin "46") (pinfunction "PA13/TMS/SWDIO_46") (pintype "bidirectional"))
      (node (ref "R6") (pin "2") (pinfunction "2_2") (pintype "passive"))
    )
    (net (code "28") (name "Net-(D2A-PA14{slash}TCK{slash}SWCLK)") (class "Default")
      (node (ref "D2") (pin "49") (pinfunction "PA14/TCK/SWCLK_49") (pintype "bidirectional"))
      (node (ref "R7") (pin "2") (pinfunction "2_2") (pintype "passive"))
    )
    (net (code "29") (name "Net-(D2A-PH0{slash}OSCIN)") (class "Default")
      (node (ref "C11") (pin "1") (pinfunction "1_1") (pintype "passive"))
      (node (ref "D2") (pin "5") (pinfunction "PH0/OSCIN_5") (pintype "bidirectional"))
      (node (ref "G1") (pin "3") (pinfunction "X2_3") (pintype "bidirectional"))
    )
    (net (code "30") (name "Net-(D2A-PH1{slash}OSCOUT)") (class "Default")
      (node (ref "C10") (pin "1") (pinfunction "1_1") (pintype "passive"))
      (node (ref "D2") (pin "6") (pinfunction "PH1/OSCOUT_6") (pintype "bidirectional"))
      (node (ref "G1") (pin "1") (pinfunction "X1_1") (pintype "bidirectional"))
    )
    (net (code "31") (name "Net-(D3-Y1)") (class "Default")
      (node (ref "D3") (pin "3") (pinfunction "Y1_3") (pintype "bidirectional"))
      (node (ref "R16") (pin "1") (pinfunction "1_1") (pintype "passive"))
    )
    (net (code "32") (name "Net-(D3-Y2)") (class "Default")
      (node (ref "D3") (pin "6") (pinfunction "Y2_6") (pintype "bidirectional"))
      (node (ref "R17") (pin "1") (pinfunction "1_1") (pintype "passive"))
    )
    (net (code "33") (name "Net-(D3-Y3)") (class "Default")
      (node (ref "D3") (pin "8") (pinfunction "Y3_8") (pintype "bidirectional"))
      (node (ref "R18") (pin "1") (pinfunction "1_1") (pintype "passive"))
    )
    (net (code "34") (name "Net-(D3-Y4)") (class "Default")
      (node (ref "D3") (pin "11") (pinfunction "Y4_11") (pintype "bidirectional"))
      (node (ref "R19") (pin "1") (pinfunction "1_1") (pintype "passive"))
    )
    (net (code "35") (name "Net-(H1-PadC)") (class "Default")
      (node (ref "H1") (pin "C") (pinfunction "C_C") (pintype "passive"))
      (node (ref "R12") (pin "2") (pinfunction "2_2") (pintype "passive"))
    )
    (net (code "36") (name "Net-(H2-PadC)") (class "Default")
      (node (ref "H2") (pin "C") (pinfunction "C_C") (pintype "passive"))
      (node (ref "R14") (pin "2") (pinfunction "2_2") (pintype "passive"))
    )
    (net (code "37") (name "Net-(H3-PadC)") (class "Default")
      (node (ref "H3") (pin "C") (pinfunction "C_C") (pintype "passive"))
      (node (ref "R13") (pin "2") (pinfunction "2_2") (pintype "passive"))
    )
    (net (code "38") (name "Net-(N1-BST)") (class "Default")
      (node (ref "C1") (pin "2") (pinfunction "2_2") (pintype "passive"))
      (node (ref "N1") (pin "6") (pinfunction "BST_6") (pintype "bidirectional"))
    )
    (net (code "39") (name "Net-(N1-FB)") (class "Default")
      (node (ref "N1") (pin "4") (pinfunction "FB_4") (pintype "bidirectional"))
      (node (ref "R1") (pin "1") (pinfunction "1_1") (pintype "passive"))
      (node (ref "R2") (pin "2") (pinfunction "2_2") (pintype "passive"))
    )
    (net (code "40") (name "Net-(N2-BST)") (class "Default")
      (node (ref "C4") (pin "2") (pinfunction "2_2") (pintype "passive"))
      (node (ref "N2") (pin "6") (pinfunction "BST_6") (pintype "bidirectional"))
    )
    (net (code "41") (name "Net-(N2-FB)") (class "Default")
      (node (ref "N2") (pin "4") (pinfunction "FB_4") (pintype "bidirectional"))
      (node (ref "R3") (pin "1") (pinfunction "1_1") (pintype "passive"))
      (node (ref "R4") (pin "2") (pinfunction "2_2") (pintype "passive"))
    )
    (net (code "42") (name "OE_N") (class "Default")
      (node (ref "D2") (pin "15") (pinfunction "PA1_15") (pintype "bidirectional"))
      (node (ref "D3") (pin "1") (pinfunction "OE1_1") (pintype "bidirectional"))
      (node (ref "D3") (pin "10") (pinfunction "OE3_10") (pintype "bidirectional"))
      (node (ref "D3") (pin "13") (pinfunction "OE4_13") (pintype "bidirectional"))
      (node (ref "D3") (pin "4") (pinfunction "OE2_4") (pintype "bidirectional"))
      (node (ref "R15") (pin "1") (pinfunction "1_1") (pintype "passive"))
    )
    (net (code "43") (name "PULSE1") (class "Default")
      (node (ref "R16") (pin "2") (pinfunction "2_2") (pintype "passive"))
      (node (ref "X4") (pin "1") (pinfunction "1_1") (pintype "passive"))
    )
    (net (code "44") (name "PULSE2") (class "Default")
      (node (ref "R18") (pin "2") (pinfunction "2_2") (pintype "passive"))
      (node (ref "X5") (pin "1") (pinfunction "1_1") (pintype "passive"))
    )
    (net (code "45") (name "PULSE_1") (class "Default")
      (node (ref "D2") (pin "16") (pinfunction "PA2_16") (pintype "bidirectional"))
      (node (ref "D3") (pin "2") (pinfunction "A1_2") (pintype "bidirectional"))
    )
    (net (code "46") (name "PULSE_2") (class "Default")
      (node (ref "D2") (pin "17") (pinfunction "PA3_17") (pintype "bidirectional"))
      (node (ref "D3") (pin "9") (pinfunction "A3_9") (pintype "bidirectional"))
    )
    (net (code "47") (name "RESET_N") (class "Default")
      (node (ref "D1") (pin "1") (pinfunction "RESET_1") (pintype "bidirectional"))
      (node (ref "D2") (pin "7") (pinfunction "RSTL_7") (pintype "bidirectional"))
      (node (ref "R5") (pin "1") (pinfunction "1_1") (pintype "passive"))
      (node (ref "X2") (pin "A1") (pinfunction "1_A1") (pintype "passive"))
    )
    (net (code "48") (name "SCL") (class "Default")
      (node (ref "D4") (pin "7") (pinfunction "SCLB_7") (pintype "bidirectional"))
      (node (ref "R9") (pin "1") (pinfunction "1_1") (pintype "passive"))
      (node (ref "X3") (pin "4") (pinfunction "4_4") (pintype "passive"))
    )
    (net (code "49") (name "SDA") (class "Default")
      (node (ref "D4") (pin "6") (pinfunction "SDAB_6") (pintype "bidirectional"))
      (node (ref "R8") (pin "1") (pinfunction "1_1") (pintype "passive"))
      (node (ref "X3") (pin "2") (pinfunction "2_2") (pintype "passive"))
    )
    (net (code "50") (name "SW3V3") (class "Default")
      (node (ref "C4") (pin "1") (pinfunction "1_1") (pintype "passive"))
      (node (ref "L2") (pin "2") (pinfunction "2_2") (pintype "passive"))
      (node (ref "N2") (pin "2") (pinfunction "SW_2") (pintype "bidirectional"))
    )
    (net (code "51") (name "SW5V") (class "Default")
      (node (ref "C1") (pin "1") (pinfunction "1_1") (pintype "passive"))
      (node (ref "L1") (pin "2") (pinfunction "2_2") (pintype "passive"))
      (node (ref "N1") (pin "2") (pinfunction "SW_2") (pintype "bidirectional"))
    )
    (net (code "52") (name "SWCLK") (class "Default")
      (node (ref "R7") (pin "1") (pinfunction "1_1") (pintype "passive"))
      (node (ref "X2") (pin "A3") (pinfunction "3_A3") (pintype "passive"))
    )
    (net (code "53") (name "SWDIO") (class "Default")
      (node (ref "R6") (pin "1") (pinfunction "1_1") (pintype "passive"))
      (node (ref "X2") (pin "A2") (pinfunction "2_A2") (pintype "passive"))
    )
    (net (code "54") (name "USART6RX") (class "Default")
      (node (ref "D2") (pin "45") (pinfunction "PA12_45") (pintype "bidirectional"))
      (node (ref "X2") (pin "A4") (pinfunction "4_A4") (pintype "passive"))
    )
    (net (code "55") (name "USART6TX") (class "Default")
      (node (ref "D2") (pin "44") (pinfunction "PA11_44") (pintype "bidirectional"))
      (node (ref "X2") (pin "A5") (pinfunction "5_A5") (pintype "passive"))
    )
    (net (code "56") (name "VCAP") (class "Default")
      (node (ref "C12") (pin "1") (pinfunction "1_1") (pintype "passive"))
      (node (ref "D2") (pin "30") (pinfunction "VCAP1_30") (pintype "bidirectional"))
    )
    (net (code "57") (name "VDDA") (class "Default")
      (node (ref "C13") (pin "1") (pinfunction "1_1") (pintype "passive"))
      (node (ref "D2") (pin "13") (pinfunction "VDDA/VREF+_13") (pintype "bidirectional"))
      (node (ref "L3") (pin "2") (pinfunction "2_2") (pintype "passive"))
    )
    (net (code "58") (name "VIN") (class "Default")
      (node (ref "R30") (pin "1") (pinfunction "1_1") (pintype "passive"))
      (node (ref "X1") (pin "1") (pinfunction "1_1") (pintype "passive"))
    )
    (net (code "59") (name "VINL") (class "Default")
      (node (ref "C29") (pin "1") (pinfunction "1_1") (pintype "passive"))
      (node (ref "L5") (pin "1") (pinfunction "1_1") (pintype "passive"))
      (node (ref "L6") (pin "2") (pinfunction "2_2") (pintype "passive"))
    )
    (net (code "60") (name "VINR") (class "Default")
      (node (ref "C28") (pin "1") (pinfunction "1_1") (pintype "passive"))
      (node (ref "L5") (pin "2") (pinfunction "2_2") (pintype "passive"))
      (node (ref "R30") (pin "2") (pinfunction "2_2") (pintype "passive"))
      (node (ref "V1") (pin "C") (pinfunction "C_C") (pintype "passive"))
    )
    (net (code "61") (name "unconnected-(D2A-PA0{slash}WKUP-Pad14)") (class "Default")
      (node (ref "D2") (pin "14") (pinfunction "PA0/WKUP_14") (pintype "bidirectional"))
    )
    (net (code "62") (name "unconnected-(D2A-PA15{slash}TDI-Pad50)") (class "Default")
      (node (ref "D2") (pin "50") (pinfunction "PA15/TDI_50") (pintype "bidirectional"))
    )
    (net (code "63") (name "unconnected-(D2A-PB3{slash}TDO-Pad55)") (class "Default")
      (node (ref "D2") (pin "55") (pinfunction "PB3/TDO_55") (pintype "bidirectional"))
    )
    (net (code "64") (name "unconnected-(D2A-PB4{slash}TRSTL-Pad56)") (class "Default")
      (node (ref "D2") (pin "56") (pinfunction "PB4/TRSTL_56") (pintype "bidirectional"))
    )
    (net (code "65") (name "unconnected-(D2A-PC14{slash}OSC32IN-Pad3)") (class "Default")
      (node (ref "D2") (pin "3") (pinfunction "PC14/OSC32IN_3") (pintype "bidirectional"))
    )
    (net (code "66") (name "unconnected-(D2A-PC15{slash}OSC32OUT-Pad4)") (class "Default")
      (node (ref "D2") (pin "4") (pinfunction "PC15/OSC32OUT_4") (pintype "bidirectional"))
    )
    (net (code "67") (name "unconnected-(D2B-PA6-Pad22)") (class "Default")
      (node (ref "D2") (pin "22") (pinfunction "PA6_22") (pintype "bidirectional"))
    )
    (net (code "68") (name "unconnected-(D2B-PA8-Pad41)") (class "Default")
      (node (ref "D2") (pin "41") (pinfunction "PA8_41") (pintype "bidirectional"))
    )
    (net (code "69") (name "unconnected-(D2B-PA9-Pad42)") (class "Default")
      (node (ref "D2") (pin "42") (pinfunction "PA9_42") (pintype "bidirectional"))
    )
    (net (code "70") (name "unconnected-(D2B-PA10-Pad43)") (class "Default")
      (node (ref "D2") (pin "43") (pinfunction "PA10_43") (pintype "bidirectional"))
    )
    (net (code "71") (name "unconnected-(D2B-PB0-Pad26)") (class "Default")
      (node (ref "D2") (pin "26") (pinfunction "PB0_26") (pintype "bidirectional"))
    )
    (net (code "72") (name "unconnected-(D2B-PB1-Pad27)") (class "Default")
      (node (ref "D2") (pin "27") (pinfunction "PB1_27") (pintype "bidirectional"))
    )
    (net (code "73") (name "unconnected-(D2B-PB5-Pad57)") (class "Default")
      (node (ref "D2") (pin "57") (pinfunction "PB5_57") (pintype "bidirectional"))
    )
    (net (code "74") (name "unconnected-(D2B-PB8-Pad61)") (class "Default")
      (node (ref "D2") (pin "61") (pinfunction "PB8_61") (pintype "bidirectional"))
    )
    (net (code "75") (name "unconnected-(D2B-PB9-Pad62)") (class "Default")
      (node (ref "D2") (pin "62") (pinfunction "PB9_62") (pintype "bidirectional"))
    )
    (net (code "76") (name "unconnected-(D2B-PB10-Pad29)") (class "Default")
      (node (ref "D2") (pin "29") (pinfunction "PB10_29") (pintype "bidirectional"))
    )
    (net (code "77") (name "unconnected-(D2B-PB12-Pad33)") (class "Default")
      (node (ref "D2") (pin "33") (pinfunction "PB12_33") (pintype "bidirectional"))
    )
    (net (code "78") (name "unconnected-(D2B-PB13-Pad34)") (class "Default")
      (node (ref "D2") (pin "34") (pinfunction "PB13_34") (pintype "bidirectional"))
    )
    (net (code "79") (name "unconnected-(D2B-PB14-Pad35)") (class "Default")
      (node (ref "D2") (pin "35") (pinfunction "PB14_35") (pintype "bidirectional"))
    )
    (net (code "80") (name "unconnected-(D2B-PB15-Pad36)") (class "Default")
      (node (ref "D2") (pin "36") (pinfunction "PB15_36") (pintype "bidirectional"))
    )
    (net (code "81") (name "unconnected-(D2B-PC0-Pad8)") (class "Default")
      (node (ref "D2") (pin "8") (pinfunction "PC0_8") (pintype "bidirectional"))
    )
    (net (code "82") (name "unconnected-(D2B-PC1-Pad9)") (class "Default")
      (node (ref "D2") (pin "9") (pinfunction "PC1_9") (pintype "bidirectional"))
    )
    (net (code "83") (name "unconnected-(D2B-PC2-Pad10)") (class "Default")
      (node (ref "D2") (pin "10") (pinfunction "PC2_10") (pintype "bidirectional"))
    )
    (net (code "84") (name "unconnected-(D2B-PC3-Pad11)") (class "Default")
      (node (ref "D2") (pin "11") (pinfunction "PC3_11") (pintype "bidirectional"))
    )
    (net (code "85") (name "unconnected-(D2B-PC4-Pad24)") (class "Default")
      (node (ref "D2") (pin "24") (pinfunction "PC4_24") (pintype "bidirectional"))
    )
    (net (code "86") (name "unconnected-(D2B-PC5-Pad25)") (class "Default")
      (node (ref "D2") (pin "25") (pinfunction "PC5_25") (pintype "bidirectional"))
    )
    (net (code "87") (name "unconnected-(D2B-PC6-Pad37)") (class "Default")
      (node (ref "D2") (pin "37") (pinfunction "PC6_37") (pintype "bidirectional"))
    )
    (net (code "88") (name "unconnected-(D2B-PC7-Pad38)") (class "Default")
      (node (ref "D2") (pin "38") (pinfunction "PC7_38") (pintype "bidirectional"))
    )
    (net (code "89") (name "unconnected-(D2B-PC13-Pad2)") (class "Default")
      (node (ref "D2") (pin "2") (pinfunction "PC13_2") (pintype "bidirectional"))
    )
    (net (code "90") (name "unconnected-(D5E-Y-Pad10)") (class "Default")
      (node (ref "D5") (pin "10") (pinfunction "Y_10") (pintype "bidirectional"))
    )
    (net (code "91") (name "unconnected-(D5F-Y-Pad12)") (class "Default")
      (node (ref "D5") (pin "12") (pinfunction "Y_12") (pintype "bidirectional"))
    )
    (net (code "92") (name "unconnected-(X2B-1-PadB1)") (class "Default")
      (node (ref "X2") (pin "B1") (pinfunction "1_B1") (pintype "passive"))
    )
  )
)
